# inverter_sch.net
KiCad netlist of a schematic drawn in Altium Designer
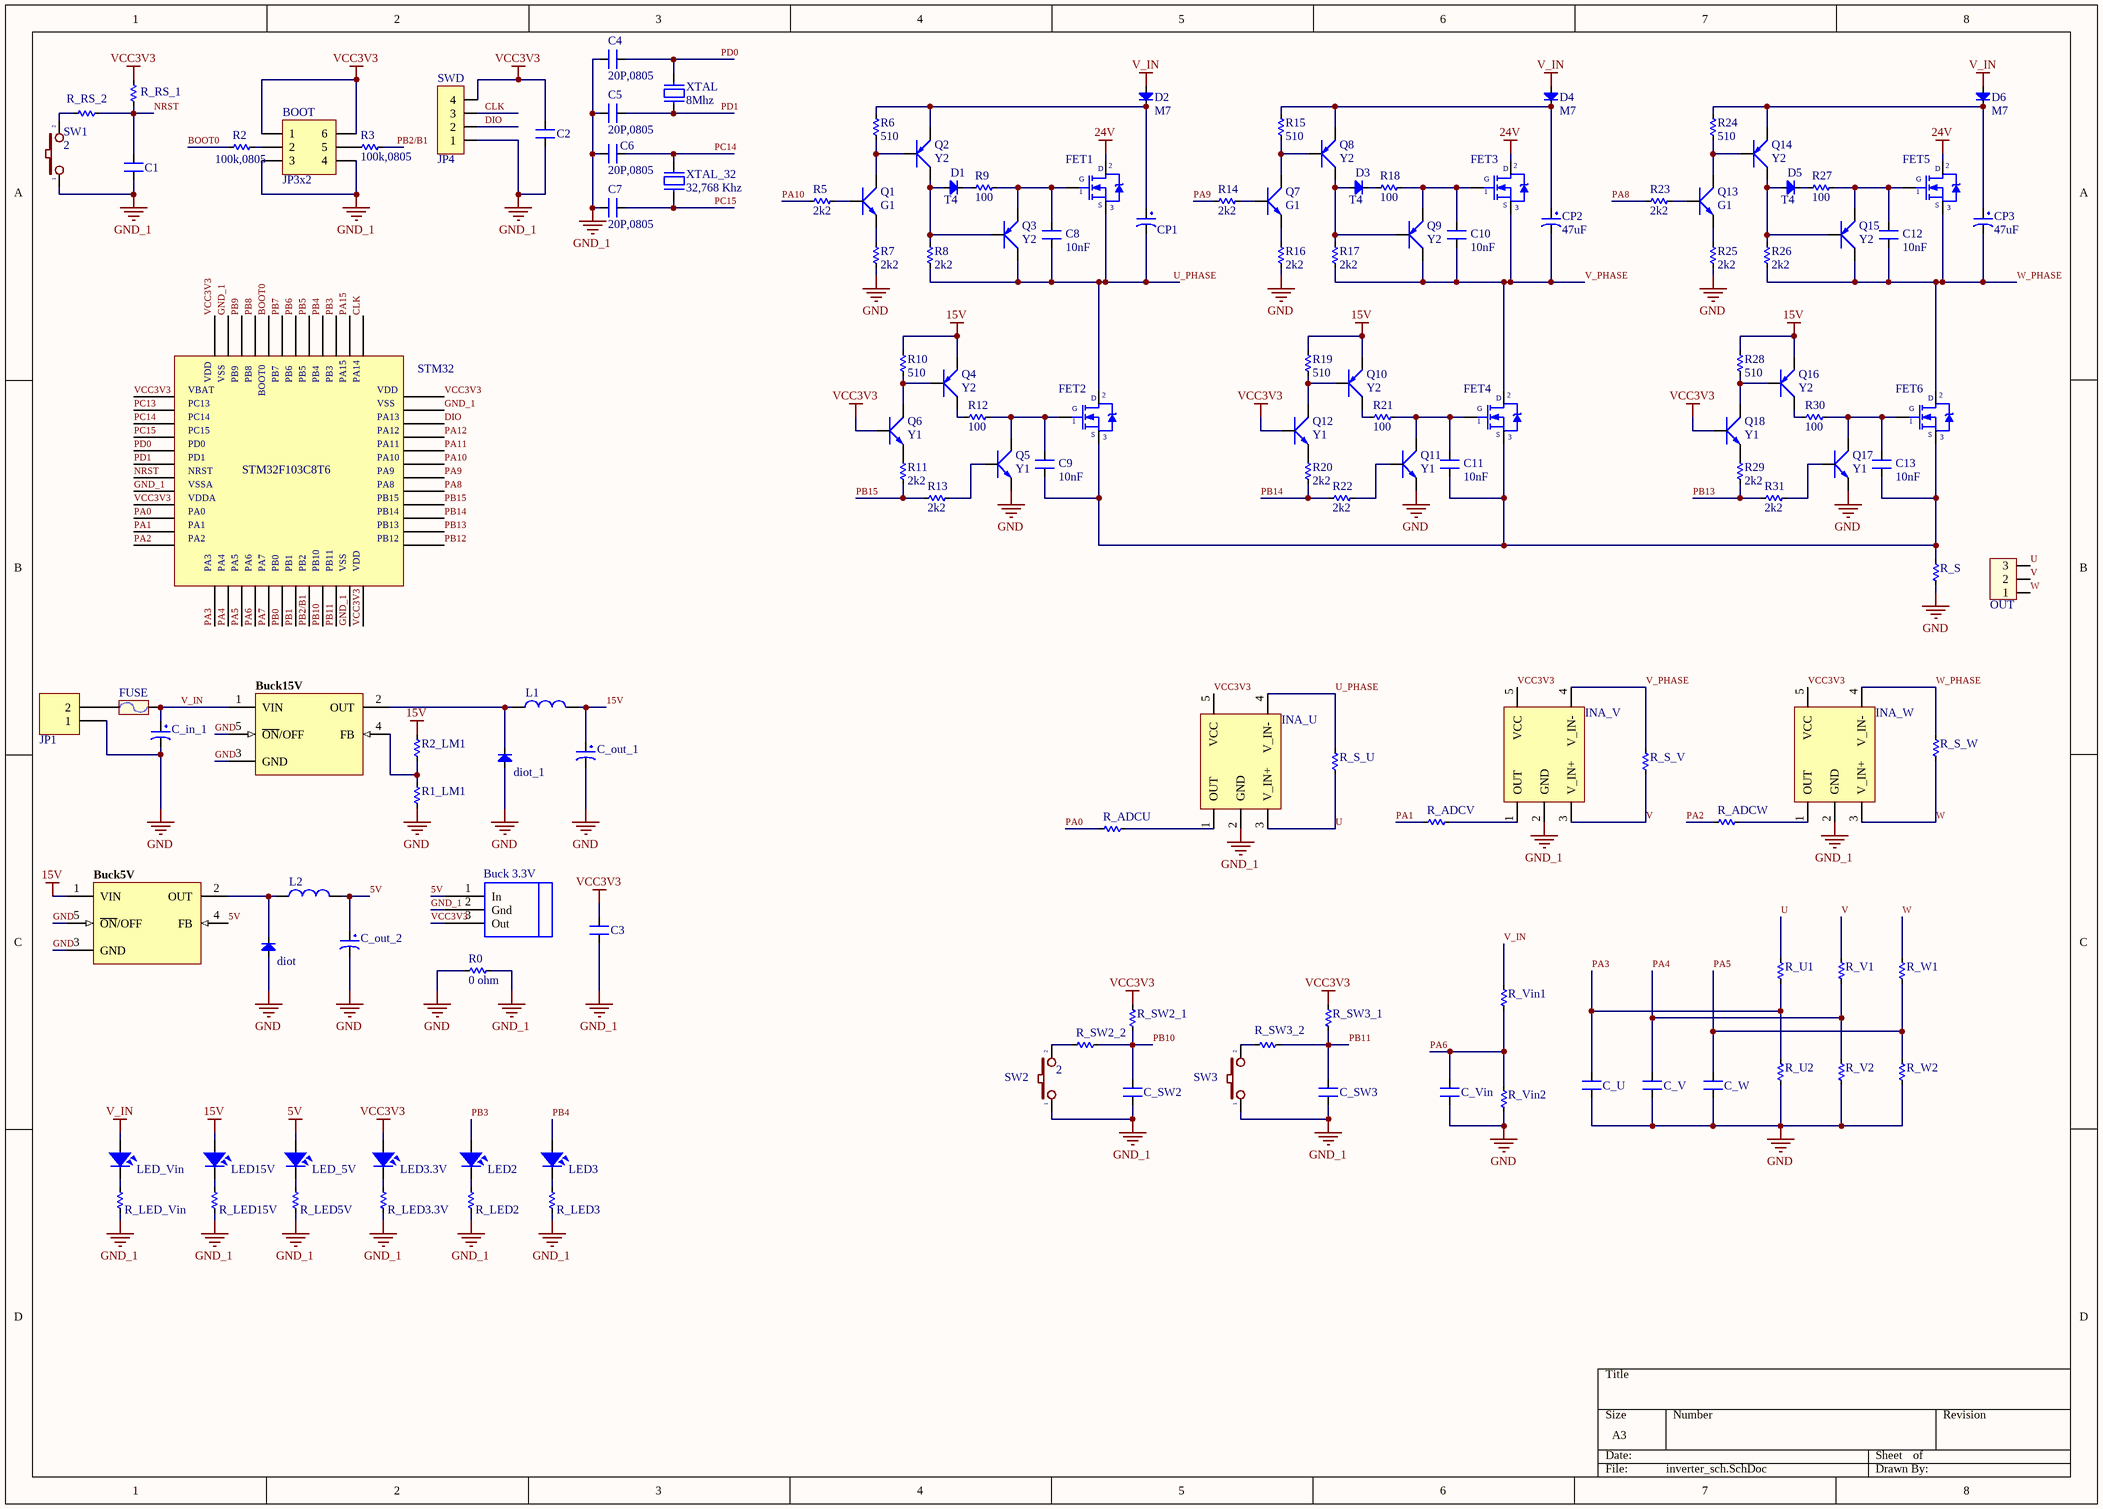
[diagram p0: inverter_sch.SchDoc]

(export (version "E")
  (design (tool "Eeschema 10.0.6"))
  (components
    (comp (ref "BOOT")
      (value "JP3x2")
      (footprint "JP3-D2T")
      (description "WR-PHD 2.54 mm Dual Socket Header")
      (fields
        (field (name "MANUFACTURER") "Würth Elektronik eiSos GmbH")
        (field (name "PARTNO") "61300621821")
        (field (name "CREATED BY") "Karrer Zheng")
      )
      (libsource (lib "LIBRARY") (part "JP3x2"))
    )
    (comp (ref "Buck 3.3V")
      (value "LM3940-3.3")
      (footprint "SOT223")
      (description "3.3 VOLT LINEAR REGULATOR SOT223")
      (fields
        (field (name "MANUFACTURER") "National Semiconductor")
        (field (name "MANUFACTURER PART NUMBER") "LM3940IMP-3.3/NOPB")
      )
      (libsource (lib "LIBRARY") (part "LM3940-3.3-SOT223"))
    )
    (comp (ref "Buck5V") (value "LM2576") (footprint "TO263") (libsource (lib "LIBRARY") (part "LM2576")))
    (comp (ref "Buck15V") (value "LM2576") (footprint "TO263") (libsource (lib "LIBRARY") (part "LM2576")))
    (comp (ref "C1") (value "104,0805") (footprint "CN-SMD-0805") (libsource (lib "LIBRARY") (part "CN")))
    (comp (ref "C2") (value "104,0805") (footprint "CN-SMD-0805") (libsource (lib "LIBRARY") (part "CN")))
    (comp (ref "C3") (value "104,0805") (footprint "CN-SMD-0805") (libsource (lib "LIBRARY") (part "CN")))
    (comp (ref "C4") (value "20P,0805") (footprint "CN-SMD-0805") (libsource (lib "LIBRARY") (part "CN")))
    (comp (ref "C5") (value "20P,0805") (footprint "CN-SMD-0805") (libsource (lib "LIBRARY") (part "CN")))
    (comp (ref "C6") (value "20P,0805") (footprint "CN-SMD-0805") (libsource (lib "LIBRARY") (part "CN")))
    (comp (ref "C7") (value "20P,0805") (footprint "CN-SMD-0805") (libsource (lib "LIBRARY") (part "CN")))
    (comp (ref "C8") (value "10nF") (footprint "CN-SMD-0805") (libsource (lib "LIBRARY") (part "CN")))
    (comp (ref "C9") (value "10nF") (footprint "CN-SMD-0805") (libsource (lib "LIBRARY") (part "CN")))
    (comp (ref "C10") (value "10nF") (footprint "CN-SMD-0805") (libsource (lib "LIBRARY") (part "CN")))
    (comp (ref "C11") (value "10nF") (footprint "CN-SMD-0805") (libsource (lib "LIBRARY") (part "CN")))
    (comp (ref "C12") (value "10nF") (footprint "CN-SMD-0805") (libsource (lib "LIBRARY") (part "CN")))
    (comp (ref "C13") (value "10nF") (footprint "CN-SMD-0805") (libsource (lib "LIBRARY") (part "CN")))
    (comp (ref "CP1")
      (value "47uF")
      (footprint "CP1/2")
      (description "Cap P  0,1uF < 22uF , 16 - 50V")
      (libsource (lib "syhaunguyen") (part "CP1"))
    )
    (comp (ref "CP2")
      (value "47uF")
      (footprint "CP1/2")
      (description "Cap P  0,1uF < 22uF , 16 - 50V")
      (libsource (lib "syhaunguyen") (part "CP1"))
    )
    (comp (ref "CP3")
      (value "47uF")
      (footprint "CP1/2")
      (description "Cap P  0,1uF < 22uF , 16 - 50V")
      (libsource (lib "syhaunguyen") (part "CP1"))
    )
    (comp (ref "C_in_1")
      (value "100uF")
      (footprint "CP1.5/3.4")
      (description "Cap 1000uF/16V - 220uF/50V")
      (libsource (lib "syhaunguyen") (part "CP4"))
    )
    (comp (ref "C_out_1")
      (value "100uF")
      (footprint "CP1.5/3.4")
      (description "Cap 1000uF/16V - 220uF/50V")
      (libsource (lib "syhaunguyen") (part "CP4"))
    )
    (comp (ref "C_out_2")
      (value "100uF")
      (footprint "CP1.5/3.4")
      (description "Cap 1000uF/16V - 220uF/50V")
      (libsource (lib "syhaunguyen") (part "CP4"))
    )
    (comp (ref "C_SW2") (value "104,0805") (footprint "CN-SMD-0805") (libsource (lib "LIBRARY") (part "CN")))
    (comp (ref "C_SW3") (value "104,0805") (footprint "CN-SMD-0805") (libsource (lib "LIBRARY") (part "CN")))
    (comp (ref "C_U") (value "XXpF") (footprint "CN-SMD-0805") (libsource (lib "LIBRARY") (part "CN")))
    (comp (ref "C_V") (value "XXpF") (footprint "CN-SMD-0805") (libsource (lib "LIBRARY") (part "CN")))
    (comp (ref "C_Vin") (value "XXpF") (footprint "CN-SMD-0805") (libsource (lib "LIBRARY") (part "CN")))
    (comp (ref "C_W") (value "XXpF") (footprint "CN-SMD-0805") (libsource (lib "LIBRARY") (part "CN")))
    (comp (ref "D1")
      (value "T4")
      (footprint "DIO-SMD-106")
      (description "Default Diode")
      (fields (field (name "PUBLISHER") "Altium Limited"))
      (libsource (lib "LIBRARY") (part "Diode SMD"))
    )
    (comp (ref "D2")
      (value "M7")
      (footprint "DIO-SMD-106")
      (description "Default Diode")
      (fields (field (name "PUBLISHER") "Altium Limited"))
      (libsource (lib "LIBRARY") (part "Diode SMD"))
    )
    (comp (ref "D3")
      (value "T4")
      (footprint "DIO-SMD-106")
      (description "Default Diode")
      (fields (field (name "PUBLISHER") "Altium Limited"))
      (libsource (lib "LIBRARY") (part "Diode SMD"))
    )
    (comp (ref "D4")
      (value "M7")
      (footprint "DIO-SMD-106")
      (description "Default Diode")
      (fields (field (name "PUBLISHER") "Altium Limited"))
      (libsource (lib "LIBRARY") (part "Diode SMD"))
    )
    (comp (ref "D5")
      (value "T4")
      (footprint "DIO-SMD-106")
      (description "Default Diode")
      (fields (field (name "PUBLISHER") "Altium Limited"))
      (libsource (lib "LIBRARY") (part "Diode SMD"))
    )
    (comp (ref "D6")
      (value "M7")
      (footprint "DIO-SMD-106")
      (description "Default Diode")
      (fields (field (name "PUBLISHER") "Altium Limited"))
      (libsource (lib "LIBRARY") (part "Diode SMD"))
    )
    (comp (ref "diot")
      (value "Diode SMD")
      (footprint "DIO-SMD-106")
      (description "Default Diode")
      (fields (field (name "PUBLISHER") "Altium Limited"))
      (libsource (lib "LIBRARY") (part "Diode SMD"))
    )
    (comp (ref "diot_1")
      (value "Diode SMD")
      (footprint "DIO-SMD-106")
      (description "Default Diode")
      (fields (field (name "PUBLISHER") "Altium Limited"))
      (libsource (lib "LIBRARY") (part "Diode SMD"))
    )
    (comp (ref "FET1")
      (value "STP80NF70")
      (footprint "QTO-220")
      (description "MOSFET N - CHANNEL 500V - 0.75 - 8A - TO-220")
      (libsource (lib "syhaunguyen") (part "IRF840"))
    )
    (comp (ref "FET2")
      (value "STP80NF70")
      (footprint "QTO-220")
      (description "MOSFET N - CHANNEL 500V - 0.75 - 8A - TO-220")
      (libsource (lib "syhaunguyen") (part "IRF840"))
    )
    (comp (ref "FET3")
      (value "STP80NF70")
      (footprint "QTO-220")
      (description "MOSFET N - CHANNEL 500V - 0.75 - 8A - TO-220")
      (libsource (lib "syhaunguyen") (part "IRF840"))
    )
    (comp (ref "FET4")
      (value "STP80NF70")
      (footprint "QTO-220")
      (description "MOSFET N - CHANNEL 500V - 0.75 - 8A - TO-220")
      (libsource (lib "syhaunguyen") (part "IRF840"))
    )
    (comp (ref "FET5")
      (value "STP80NF70")
      (footprint "QTO-220")
      (description "MOSFET N - CHANNEL 500V - 0.75 - 8A - TO-220")
      (libsource (lib "syhaunguyen") (part "IRF840"))
    )
    (comp (ref "FET6")
      (value "STP80NF70")
      (footprint "QTO-220")
      (description "MOSFET N - CHANNEL 500V - 0.75 - 8A - TO-220")
      (libsource (lib "syhaunguyen") (part "IRF840"))
    )
    (comp (ref "FUSE")
      (value "F1A")
      (footprint "Fuse1")
      (description "Fuse")
      (fields (field (name "DESIGNED BY") "VanDungEvn"))
      (libsource (lib "LIBRARY") (part "Fuse"))
    )
    (comp (ref "INA_U")
      (value "INA193_4_5")
      (footprint "SOT95_SOT23")
      (libsource (lib "Schlib1") (part "INA193_4_5"))
    )
    (comp (ref "INA_V")
      (value "INA193_4_5")
      (footprint "SOT95_SOT23")
      (libsource (lib "Schlib1") (part "INA193_4_5"))
    )
    (comp (ref "INA_W")
      (value "INA193_4_5")
      (footprint "SOT95_SOT23")
      (libsource (lib "Schlib1") (part "INA193_4_5"))
    )
    (comp (ref "JP1")
      (value "Header 2_1")
      (footprint "HED2")
      (description "Header, 2-Pin")
      (fields (field (name "MANUFACTURER") "Generic Components"))
      (libsource (lib "syhaunguyen") (part "Header 2_1"))
    )
    (comp (ref "L1")
      (value "100mH")
      (footprint "L/0.4")
      (description "Inductor")
      (libsource (lib "syhaunguyen") (part "L1"))
    )
    (comp (ref "L2")
      (value "100mH")
      (footprint "L/0.4")
      (description "Inductor")
      (libsource (lib "syhaunguyen") (part "L1"))
    )
    (comp (ref "LED2")
      (value "power 0805")
      (footprint "LED-0805-Blue")
      (libsource (lib "LIBRARY") (part "LED SMD"))
    )
    (comp (ref "LED3")
      (value "power 0805")
      (footprint "LED-0805-Blue")
      (libsource (lib "LIBRARY") (part "LED SMD"))
    )
    (comp (ref "LED3.3V")
      (value "power 0805")
      (footprint "LED-0805-Blue")
      (libsource (lib "LIBRARY") (part "LED SMD"))
    )
    (comp (ref "LED15V")
      (value "power 0805")
      (footprint "LED-0805-Blue")
      (libsource (lib "LIBRARY") (part "LED SMD"))
    )
    (comp (ref "LED_5V")
      (value "power 0805")
      (footprint "LED-0805-Blue")
      (libsource (lib "LIBRARY") (part "LED SMD"))
    )
    (comp (ref "LED_Vin")
      (value "power 0805")
      (footprint "LED-0805-Blue")
      (libsource (lib "LIBRARY") (part "LED SMD"))
    )
    (comp (ref "OUT")
      (value "Header 3")
      (footprint "HED3B")
      (description "Header 3 (Green)")
      (libsource (lib "syhaunguyen") (part "Hed3"))
    )
    (comp (ref "Q1")
      (value "G1")
      (footprint "SOT23B")
      (description "NPN 600mW, ECB")
      (libsource (lib "syhaunguyen") (part "C1815"))
    )
    (comp (ref "Q2")
      (value "Y2")
      (footprint "SOT23B")
      (description "PNP 600mW, ECB")
      (libsource (lib "syhaunguyen") (part "A1015"))
    )
    (comp (ref "Q3")
      (value "Y2")
      (footprint "SOT23B")
      (description "PNP 600mW, ECB")
      (libsource (lib "syhaunguyen") (part "A1015"))
    )
    (comp (ref "Q4")
      (value "Y2")
      (footprint "SOT23B")
      (description "PNP 600mW, ECB")
      (libsource (lib "syhaunguyen") (part "A1015"))
    )
    (comp (ref "Q5")
      (value "Y1")
      (footprint "SOT23B")
      (description "NPN 600mW, ECB")
      (libsource (lib "syhaunguyen") (part "C1815"))
    )
    (comp (ref "Q6")
      (value "Y1")
      (footprint "SOT23B")
      (description "NPN 600mW, ECB")
      (libsource (lib "syhaunguyen") (part "C1815"))
    )
    (comp (ref "Q7")
      (value "G1")
      (footprint "SOT23B")
      (description "NPN 600mW, ECB")
      (libsource (lib "syhaunguyen") (part "C1815"))
    )
    (comp (ref "Q8")
      (value "Y2")
      (footprint "SOT23B")
      (description "PNP 600mW, ECB")
      (libsource (lib "syhaunguyen") (part "A1015"))
    )
    (comp (ref "Q9")
      (value "Y2")
      (footprint "SOT23B")
      (description "PNP 600mW, ECB")
      (libsource (lib "syhaunguyen") (part "A1015"))
    )
    (comp (ref "Q10")
      (value "Y2")
      (footprint "SOT23B")
      (description "PNP 600mW, ECB")
      (libsource (lib "syhaunguyen") (part "A1015"))
    )
    (comp (ref "Q11")
      (value "Y1")
      (footprint "SOT23B")
      (description "NPN 600mW, ECB")
      (libsource (lib "syhaunguyen") (part "C1815"))
    )
    (comp (ref "Q12")
      (value "Y1")
      (footprint "SOT23B")
      (description "NPN 600mW, ECB")
      (libsource (lib "syhaunguyen") (part "C1815"))
    )
    (comp (ref "Q13")
      (value "G1")
      (footprint "SOT23B")
      (description "NPN 600mW, ECB")
      (libsource (lib "syhaunguyen") (part "C1815"))
    )
    (comp (ref "Q14")
      (value "Y2")
      (footprint "SOT23B")
      (description "PNP 600mW, ECB")
      (libsource (lib "syhaunguyen") (part "A1015"))
    )
    (comp (ref "Q15")
      (value "Y2")
      (footprint "SOT23B")
      (description "PNP 600mW, ECB")
      (libsource (lib "syhaunguyen") (part "A1015"))
    )
    (comp (ref "Q16")
      (value "Y2")
      (footprint "SOT23B")
      (description "PNP 600mW, ECB")
      (libsource (lib "syhaunguyen") (part "A1015"))
    )
    (comp (ref "Q17")
      (value "Y1")
      (footprint "SOT23B")
      (description "NPN 600mW, ECB")
      (libsource (lib "syhaunguyen") (part "C1815"))
    )
    (comp (ref "Q18")
      (value "Y1")
      (footprint "SOT23B")
      (description "NPN 600mW, ECB")
      (libsource (lib "syhaunguyen") (part "C1815"))
    )
    (comp (ref "R0")
      (value "0 ohm")
      (footprint "RES-SMD-1206")
      (description "Resistor")
      (fields
        (field (name "MANUFACTURER") "Generic Components")
        (field (name "PUBLISHER") "Altium Hobart Technology Centre")
      )
      (libsource (lib "LIBRARY") (part "Res-SMD"))
    )
    (comp (ref "R1_LM1")
      (value "Res")
      (footprint "RES-SMD-0805")
      (description "Resistor")
      (fields
        (field (name "MANUFACTURER") "Generic Components")
        (field (name "PUBLISHER") "Altium Hobart Technology Centre")
      )
      (libsource (lib "LIBRARY") (part "Res-SMD"))
    )
    (comp (ref "R2")
      (value "100k,0805")
      (footprint "RES-SMD-0805")
      (description "Resistor")
      (fields
        (field (name "MANUFACTURER") "Generic Components")
        (field (name "PUBLISHER") "Altium Hobart Technology Centre")
      )
      (libsource (lib "LIBRARY") (part "Res-SMD"))
    )
    (comp (ref "R2_LM1")
      (value "Res")
      (footprint "RES-SMD-0805")
      (description "Resistor")
      (fields
        (field (name "MANUFACTURER") "Generic Components")
        (field (name "PUBLISHER") "Altium Hobart Technology Centre")
      )
      (libsource (lib "LIBRARY") (part "Res-SMD"))
    )
    (comp (ref "R3")
      (value "100k,0805")
      (footprint "RES-SMD-0805")
      (description "Resistor")
      (fields
        (field (name "MANUFACTURER") "Generic Components")
        (field (name "PUBLISHER") "Altium Hobart Technology Centre")
      )
      (libsource (lib "LIBRARY") (part "Res-SMD"))
    )
    (comp (ref "R5")
      (value "2k2")
      (footprint "RES-SMD-0805")
      (description "Resistor")
      (fields
        (field (name "MANUFACTURER") "Generic Components")
        (field (name "PUBLISHER") "Altium Hobart Technology Centre")
      )
      (libsource (lib "LIBRARY") (part "Res-SMD"))
    )
    (comp (ref "R6")
      (value "510")
      (footprint "RES-SMD-0805")
      (description "Resistor")
      (fields
        (field (name "MANUFACTURER") "Generic Components")
        (field (name "PUBLISHER") "Altium Hobart Technology Centre")
      )
      (libsource (lib "LIBRARY") (part "Res-SMD"))
    )
    (comp (ref "R7")
      (value "2k2")
      (footprint "RES-SMD-0805")
      (description "Resistor")
      (fields
        (field (name "MANUFACTURER") "Generic Components")
        (field (name "PUBLISHER") "Altium Hobart Technology Centre")
      )
      (libsource (lib "LIBRARY") (part "Res-SMD"))
    )
    (comp (ref "R8")
      (value "2k2")
      (footprint "RES-SMD-0805")
      (description "Resistor")
      (fields
        (field (name "MANUFACTURER") "Generic Components")
        (field (name "PUBLISHER") "Altium Hobart Technology Centre")
      )
      (libsource (lib "LIBRARY") (part "Res-SMD"))
    )
    (comp (ref "R9")
      (value "100")
      (footprint "RES-SMD-0805")
      (description "Resistor")
      (fields
        (field (name "MANUFACTURER") "Generic Components")
        (field (name "PUBLISHER") "Altium Hobart Technology Centre")
      )
      (libsource (lib "LIBRARY") (part "Res-SMD"))
    )
    (comp (ref "R10")
      (value "510")
      (footprint "RES-SMD-0805")
      (description "Resistor")
      (fields
        (field (name "MANUFACTURER") "Generic Components")
        (field (name "PUBLISHER") "Altium Hobart Technology Centre")
      )
      (libsource (lib "LIBRARY") (part "Res-SMD"))
    )
    (comp (ref "R11")
      (value "2k2")
      (footprint "RES-SMD-0805")
      (description "Resistor")
      (fields
        (field (name "MANUFACTURER") "Generic Components")
        (field (name "PUBLISHER") "Altium Hobart Technology Centre")
      )
      (libsource (lib "LIBRARY") (part "Res-SMD"))
    )
    (comp (ref "R12")
      (value "100")
      (footprint "RES-SMD-0805")
      (description "Resistor")
      (fields
        (field (name "MANUFACTURER") "Generic Components")
        (field (name "PUBLISHER") "Altium Hobart Technology Centre")
      )
      (libsource (lib "LIBRARY") (part "Res-SMD"))
    )
    (comp (ref "R13")
      (value "2k2")
      (footprint "RES-SMD-0805")
      (description "Resistor")
      (fields
        (field (name "MANUFACTURER") "Generic Components")
        (field (name "PUBLISHER") "Altium Hobart Technology Centre")
      )
      (libsource (lib "LIBRARY") (part "Res-SMD"))
    )
    (comp (ref "R14")
      (value "2k2")
      (footprint "RES-SMD-0805")
      (description "Resistor")
      (fields
        (field (name "MANUFACTURER") "Generic Components")
        (field (name "PUBLISHER") "Altium Hobart Technology Centre")
      )
      (libsource (lib "LIBRARY") (part "Res-SMD"))
    )
    (comp (ref "R15")
      (value "510")
      (footprint "RES-SMD-0805")
      (description "Resistor")
      (fields
        (field (name "MANUFACTURER") "Generic Components")
        (field (name "PUBLISHER") "Altium Hobart Technology Centre")
      )
      (libsource (lib "LIBRARY") (part "Res-SMD"))
    )
    (comp (ref "R16")
      (value "2k2")
      (footprint "RES-SMD-0805")
      (description "Resistor")
      (fields
        (field (name "MANUFACTURER") "Generic Components")
        (field (name "PUBLISHER") "Altium Hobart Technology Centre")
      )
      (libsource (lib "LIBRARY") (part "Res-SMD"))
    )
    (comp (ref "R17")
      (value "2k2")
      (footprint "RES-SMD-0805")
      (description "Resistor")
      (fields
        (field (name "MANUFACTURER") "Generic Components")
        (field (name "PUBLISHER") "Altium Hobart Technology Centre")
      )
      (libsource (lib "LIBRARY") (part "Res-SMD"))
    )
    (comp (ref "R18")
      (value "100")
      (footprint "RES-SMD-0805")
      (description "Resistor")
      (fields
        (field (name "MANUFACTURER") "Generic Components")
        (field (name "PUBLISHER") "Altium Hobart Technology Centre")
      )
      (libsource (lib "LIBRARY") (part "Res-SMD"))
    )
    (comp (ref "R19")
      (value "510")
      (footprint "RES-SMD-0805")
      (description "Resistor")
      (fields
        (field (name "MANUFACTURER") "Generic Components")
        (field (name "PUBLISHER") "Altium Hobart Technology Centre")
      )
      (libsource (lib "LIBRARY") (part "Res-SMD"))
    )
    (comp (ref "R20")
      (value "2k2")
      (footprint "RES-SMD-0805")
      (description "Resistor")
      (fields
        (field (name "MANUFACTURER") "Generic Components")
        (field (name "PUBLISHER") "Altium Hobart Technology Centre")
      )
      (libsource (lib "LIBRARY") (part "Res-SMD"))
    )
    (comp (ref "R21")
      (value "100")
      (footprint "RES-SMD-0805")
      (description "Resistor")
      (fields
        (field (name "MANUFACTURER") "Generic Components")
        (field (name "PUBLISHER") "Altium Hobart Technology Centre")
      )
      (libsource (lib "LIBRARY") (part "Res-SMD"))
    )
    (comp (ref "R22")
      (value "2k2")
      (footprint "RES-SMD-0805")
      (description "Resistor")
      (fields
        (field (name "MANUFACTURER") "Generic Components")
        (field (name "PUBLISHER") "Altium Hobart Technology Centre")
      )
      (libsource (lib "LIBRARY") (part "Res-SMD"))
    )
    (comp (ref "R23")
      (value "2k2")
      (footprint "RES-SMD-0805")
      (description "Resistor")
      (fields
        (field (name "MANUFACTURER") "Generic Components")
        (field (name "PUBLISHER") "Altium Hobart Technology Centre")
      )
      (libsource (lib "LIBRARY") (part "Res-SMD"))
    )
    (comp (ref "R24")
      (value "510")
      (footprint "RES-SMD-0805")
      (description "Resistor")
      (fields
        (field (name "MANUFACTURER") "Generic Components")
        (field (name "PUBLISHER") "Altium Hobart Technology Centre")
      )
      (libsource (lib "LIBRARY") (part "Res-SMD"))
    )
    (comp (ref "R25")
      (value "2k2")
      (footprint "RES-SMD-0805")
      (description "Resistor")
      (fields
        (field (name "MANUFACTURER") "Generic Components")
        (field (name "PUBLISHER") "Altium Hobart Technology Centre")
      )
      (libsource (lib "LIBRARY") (part "Res-SMD"))
    )
    (comp (ref "R26")
      (value "2k2")
      (footprint "RES-SMD-0805")
      (description "Resistor")
      (fields
        (field (name "MANUFACTURER") "Generic Components")
        (field (name "PUBLISHER") "Altium Hobart Technology Centre")
      )
      (libsource (lib "LIBRARY") (part "Res-SMD"))
    )
    (comp (ref "R27")
      (value "100")
      (footprint "RES-SMD-0805")
      (description "Resistor")
      (fields
        (field (name "MANUFACTURER") "Generic Components")
        (field (name "PUBLISHER") "Altium Hobart Technology Centre")
      )
      (libsource (lib "LIBRARY") (part "Res-SMD"))
    )
    (comp (ref "R28")
      (value "510")
      (footprint "RES-SMD-0805")
      (description "Resistor")
      (fields
        (field (name "MANUFACTURER") "Generic Components")
        (field (name "PUBLISHER") "Altium Hobart Technology Centre")
      )
      (libsource (lib "LIBRARY") (part "Res-SMD"))
    )
    (comp (ref "R29")
      (value "2k2")
      (footprint "RES-SMD-0805")
      (description "Resistor")
      (fields
        (field (name "MANUFACTURER") "Generic Components")
        (field (name "PUBLISHER") "Altium Hobart Technology Centre")
      )
      (libsource (lib "LIBRARY") (part "Res-SMD"))
    )
    (comp (ref "R30")
      (value "100")
      (footprint "RES-SMD-0805")
      (description "Resistor")
      (fields
        (field (name "MANUFACTURER") "Generic Components")
        (field (name "PUBLISHER") "Altium Hobart Technology Centre")
      )
      (libsource (lib "LIBRARY") (part "Res-SMD"))
    )
    (comp (ref "R31")
      (value "2k2")
      (footprint "RES-SMD-0805")
      (description "Resistor")
      (fields
        (field (name "MANUFACTURER") "Generic Components")
        (field (name "PUBLISHER") "Altium Hobart Technology Centre")
      )
      (libsource (lib "LIBRARY") (part "Res-SMD"))
    )
    (comp (ref "R_ADCU")
      (value "Res")
      (footprint "RES-SMD-0805")
      (description "Resistor")
      (fields
        (field (name "MANUFACTURER") "Generic Components")
        (field (name "PUBLISHER") "Altium Hobart Technology Centre")
      )
      (libsource (lib "LIBRARY") (part "Res-SMD"))
    )
    (comp (ref "R_ADCV")
      (value "Res")
      (footprint "RES-SMD-0805")
      (description "Resistor")
      (fields
        (field (name "MANUFACTURER") "Generic Components")
        (field (name "PUBLISHER") "Altium Hobart Technology Centre")
      )
      (libsource (lib "LIBRARY") (part "Res-SMD"))
    )
    (comp (ref "R_ADCW")
      (value "Res")
      (footprint "RES-SMD-0805")
      (description "Resistor")
      (fields
        (field (name "MANUFACTURER") "Generic Components")
        (field (name "PUBLISHER") "Altium Hobart Technology Centre")
      )
      (libsource (lib "LIBRARY") (part "Res-SMD"))
    )
    (comp (ref "R_LED2")
      (value "510,0805")
      (footprint "RES-SMD-0805")
      (description "Resistor")
      (fields
        (field (name "MANUFACTURER") "Generic Components")
        (field (name "PUBLISHER") "Altium Hobart Technology Centre")
      )
      (libsource (lib "LIBRARY") (part "Res-SMD"))
    )
    (comp (ref "R_LED3")
      (value "510,0805")
      (footprint "RES-SMD-0805")
      (description "Resistor")
      (fields
        (field (name "MANUFACTURER") "Generic Components")
        (field (name "PUBLISHER") "Altium Hobart Technology Centre")
      )
      (libsource (lib "LIBRARY") (part "Res-SMD"))
    )
    (comp (ref "R_LED3.3V")
      (value "510,0805")
      (footprint "RES-SMD-0805")
      (description "Resistor")
      (fields
        (field (name "MANUFACTURER") "Generic Components")
        (field (name "PUBLISHER") "Altium Hobart Technology Centre")
      )
      (libsource (lib "LIBRARY") (part "Res-SMD"))
    )
    (comp (ref "R_LED5V")
      (value "510,0805")
      (footprint "RES-SMD-0805")
      (description "Resistor")
      (fields
        (field (name "MANUFACTURER") "Generic Components")
        (field (name "PUBLISHER") "Altium Hobart Technology Centre")
      )
      (libsource (lib "LIBRARY") (part "Res-SMD"))
    )
    (comp (ref "R_LED15V")
      (value "510,0805")
      (footprint "RES-SMD-0805")
      (description "Resistor")
      (fields
        (field (name "MANUFACTURER") "Generic Components")
        (field (name "PUBLISHER") "Altium Hobart Technology Centre")
      )
      (libsource (lib "LIBRARY") (part "Res-SMD"))
    )
    (comp (ref "R_LED_Vin")
      (value "510,0805")
      (footprint "RES-SMD-0805")
      (description "Resistor")
      (fields
        (field (name "MANUFACTURER") "Generic Components")
        (field (name "PUBLISHER") "Altium Hobart Technology Centre")
      )
      (libsource (lib "LIBRARY") (part "Res-SMD"))
    )
    (comp (ref "R_RS_1")
      (value "10k,0805")
      (footprint "RES-SMD-0805")
      (description "Resistor")
      (fields
        (field (name "MANUFACTURER") "Generic Components")
        (field (name "PUBLISHER") "Altium Hobart Technology Centre")
      )
      (libsource (lib "LIBRARY") (part "Res-SMD"))
    )
    (comp (ref "R_RS_2")
      (value "10k,0805")
      (footprint "RES-SMD-0805")
      (description "Resistor")
      (fields
        (field (name "MANUFACTURER") "Generic Components")
        (field (name "PUBLISHER") "Altium Hobart Technology Centre")
      )
      (libsource (lib "LIBRARY") (part "Res-SMD"))
    )
    (comp (ref "R_S")
      (value "Res")
      (footprint "RES-SMD-2512")
      (description "Resistor")
      (fields
        (field (name "MANUFACTURER") "Generic Components")
        (field (name "PUBLISHER") "Altium Hobart Technology Centre")
      )
      (libsource (lib "LIBRARY") (part "Res-SMD"))
    )
    (comp (ref "R_SW2_1")
      (value "10k,0805")
      (footprint "RES-SMD-0805")
      (description "Resistor")
      (fields
        (field (name "MANUFACTURER") "Generic Components")
        (field (name "PUBLISHER") "Altium Hobart Technology Centre")
      )
      (libsource (lib "LIBRARY") (part "Res-SMD"))
    )
    (comp (ref "R_SW2_2")
      (value "10k,0805")
      (footprint "RES-SMD-0805")
      (description "Resistor")
      (fields
        (field (name "MANUFACTURER") "Generic Components")
        (field (name "PUBLISHER") "Altium Hobart Technology Centre")
      )
      (libsource (lib "LIBRARY") (part "Res-SMD"))
    )
    (comp (ref "R_SW3_1")
      (value "10k,0805")
      (footprint "RES-SMD-0805")
      (description "Resistor")
      (fields
        (field (name "MANUFACTURER") "Generic Components")
        (field (name "PUBLISHER") "Altium Hobart Technology Centre")
      )
      (libsource (lib "LIBRARY") (part "Res-SMD"))
    )
    (comp (ref "R_SW3_2")
      (value "10k,0805")
      (footprint "RES-SMD-0805")
      (description "Resistor")
      (fields
        (field (name "MANUFACTURER") "Generic Components")
        (field (name "PUBLISHER") "Altium Hobart Technology Centre")
      )
      (libsource (lib "LIBRARY") (part "Res-SMD"))
    )
    (comp (ref "R_S_U")
      (value "Res")
      (footprint "RES-SMD-2512")
      (description "Resistor")
      (fields
        (field (name "MANUFACTURER") "Generic Components")
        (field (name "PUBLISHER") "Altium Hobart Technology Centre")
      )
      (libsource (lib "LIBRARY") (part "Res-SMD"))
    )
    (comp (ref "R_S_V")
      (value "Res")
      (footprint "RES-SMD-2512")
      (description "Resistor")
      (fields
        (field (name "MANUFACTURER") "Generic Components")
        (field (name "PUBLISHER") "Altium Hobart Technology Centre")
      )
      (libsource (lib "LIBRARY") (part "Res-SMD"))
    )
    (comp (ref "R_S_W")
      (value "Res")
      (footprint "RES-SMD-2512")
      (description "Resistor")
      (fields
        (field (name "MANUFACTURER") "Generic Components")
        (field (name "PUBLISHER") "Altium Hobart Technology Centre")
      )
      (libsource (lib "LIBRARY") (part "Res-SMD"))
    )
    (comp (ref "R_U1")
      (value "Res")
      (footprint "RES-SMD-0805")
      (description "Resistor")
      (fields
        (field (name "MANUFACTURER") "Generic Components")
        (field (name "PUBLISHER") "Altium Hobart Technology Centre")
      )
      (libsource (lib "LIBRARY") (part "Res-SMD"))
    )
    (comp (ref "R_U2")
      (value "Res")
      (footprint "RES-SMD-0805")
      (description "Resistor")
      (fields
        (field (name "MANUFACTURER") "Generic Components")
        (field (name "PUBLISHER") "Altium Hobart Technology Centre")
      )
      (libsource (lib "LIBRARY") (part "Res-SMD"))
    )
    (comp (ref "R_V1")
      (value "Res")
      (footprint "RES-SMD-0805")
      (description "Resistor")
      (fields
        (field (name "MANUFACTURER") "Generic Components")
        (field (name "PUBLISHER") "Altium Hobart Technology Centre")
      )
      (libsource (lib "LIBRARY") (part "Res-SMD"))
    )
    (comp (ref "R_V2")
      (value "Res")
      (footprint "RES-SMD-0805")
      (description "Resistor")
      (fields
        (field (name "MANUFACTURER") "Generic Components")
        (field (name "PUBLISHER") "Altium Hobart Technology Centre")
      )
      (libsource (lib "LIBRARY") (part "Res-SMD"))
    )
    (comp (ref "R_Vin1")
      (value "Res")
      (footprint "RES-SMD-0805")
      (description "Resistor")
      (fields
        (field (name "MANUFACTURER") "Generic Components")
        (field (name "PUBLISHER") "Altium Hobart Technology Centre")
      )
      (libsource (lib "LIBRARY") (part "Res-SMD"))
    )
    (comp (ref "R_Vin2")
      (value "Res")
      (footprint "RES-SMD-0805")
      (description "Resistor")
      (fields
        (field (name "MANUFACTURER") "Generic Components")
        (field (name "PUBLISHER") "Altium Hobart Technology Centre")
      )
      (libsource (lib "LIBRARY") (part "Res-SMD"))
    )
    (comp (ref "R_W1")
      (value "Res")
      (footprint "RES-SMD-0805")
      (description "Resistor")
      (fields
        (field (name "MANUFACTURER") "Generic Components")
        (field (name "PUBLISHER") "Altium Hobart Technology Centre")
      )
      (libsource (lib "LIBRARY") (part "Res-SMD"))
    )
    (comp (ref "R_W2")
      (value "Res")
      (footprint "RES-SMD-0805")
      (description "Resistor")
      (fields
        (field (name "MANUFACTURER") "Generic Components")
        (field (name "PUBLISHER") "Altium Hobart Technology Centre")
      )
      (libsource (lib "LIBRARY") (part "Res-SMD"))
    )
    (comp (ref "STM32")
      (value "STM32F103C8T6")
      (footprint "LQFP 48")
      (fields (field (name "MANUFACTURER") "STMicroelectronics"))
      (libsource (lib "Schlib1") (part "STM32F103C8T6"))
    )
    (comp (ref "SW1")
      (value "2")
      (footprint "SW1-SMD")
      (description "Switch button 2 pin")
      (libsource (lib "LIBRARY") (part "SW2"))
    )
    (comp (ref "SW2")
      (value "2")
      (footprint "SW1-SMD")
      (description "Switch button 2 pin")
      (libsource (lib "LIBRARY") (part "SW2"))
    )
    (comp (ref "SW3")
      (value "2")
      (footprint "SW1-SMD")
      (description "Switch button 2 pin")
      (libsource (lib "LIBRARY") (part "SW2"))
    )
    (comp (ref "SWD")
      (value "JP4")
      (footprint "JP4-C1T")
      (description "WR-PHD 2.54 mm Angled Socket Header")
      (fields
        (field (name "MANUFACTURER") "Würth Elektronik eiSos GmbH")
        (field (name "PARTNO") "613004143121")
        (field (name "CREATED BY") "Karrer Zheng")
      )
      (libsource (lib "LIBRARY") (part "JP4"))
    )
    (comp (ref "XTAL")
      (value "8Mhz")
      (footprint "XT2")
      (description "Crystal, 32.768 KHz, -40 to 85 degC, 3.2 x 1.5 x 0.9 mm SMD")
      (libsource (lib "LIBRARY") (part "XT2"))
    )
    (comp (ref "XTAL_32")
      (value "32,768 Khz")
      (footprint "XT32k")
      (description "Crystal 32,768kHz for timer real")
      (libsource (lib "syhaunguyen") (part "XT32k"))
    )
  )
  (nets
    (net (code "1") (name "/BOOT0") (class "Default")
      (node (ref "R2") (pin "1") (pinfunction "1_1") (pintype "passive"))
      (node (ref "STM32") (pin "44") (pinfunction "44_44") (pintype "passive"))
    )
    (net (code "2") (name "/CLK") (class "Default")
      (node (ref "STM32") (pin "37") (pinfunction "37_37") (pintype "passive"))
      (node (ref "SWD") (pin "3") (pinfunction "3_3") (pintype "passive"))
    )
    (net (code "3") (name "/DIO") (class "Default")
      (node (ref "STM32") (pin "34") (pinfunction "34_34") (pintype "passive"))
      (node (ref "SWD") (pin "2") (pinfunction "2_2") (pintype "passive"))
    )
    (net (code "4") (name "/NRST") (class "Default")
      (node (ref "C1") (pin "2") (pinfunction "2_2") (pintype "passive"))
      (node (ref "R_RS_1") (pin "2") (pinfunction "2_2") (pintype "passive"))
      (node (ref "R_RS_2") (pin "1") (pinfunction "1_1") (pintype "passive"))
      (node (ref "STM32") (pin "7") (pinfunction "7_7") (pintype "passive"))
    )
    (net (code "5") (name "/PA0") (class "Default")
      (node (ref "R_ADCU") (pin "2") (pinfunction "2_2") (pintype "passive"))
      (node (ref "STM32") (pin "10") (pinfunction "10_10") (pintype "passive"))
    )
    (net (code "6") (name "/PA1") (class "Default")
      (node (ref "R_ADCV") (pin "2") (pinfunction "2_2") (pintype "passive"))
      (node (ref "STM32") (pin "11") (pinfunction "11_11") (pintype "passive"))
    )
    (net (code "7") (name "/PA2") (class "Default")
      (node (ref "R_ADCW") (pin "2") (pinfunction "2_2") (pintype "passive"))
      (node (ref "STM32") (pin "12") (pinfunction "12_12") (pintype "passive"))
    )
    (net (code "8") (name "/PA3") (class "Default")
      (node (ref "C_U") (pin "2") (pinfunction "2_2") (pintype "passive"))
      (node (ref "R_U1") (pin "2") (pinfunction "2_2") (pintype "passive"))
      (node (ref "R_U2") (pin "1") (pinfunction "1_1") (pintype "passive"))
      (node (ref "STM32") (pin "13") (pinfunction "13_13") (pintype "passive"))
    )
    (net (code "9") (name "/PA4") (class "Default")
      (node (ref "C_V") (pin "2") (pinfunction "2_2") (pintype "passive"))
      (node (ref "R_V1") (pin "2") (pinfunction "2_2") (pintype "passive"))
      (node (ref "R_V2") (pin "1") (pinfunction "1_1") (pintype "passive"))
      (node (ref "STM32") (pin "14") (pinfunction "14_14") (pintype "passive"))
    )
    (net (code "10") (name "/PA5") (class "Default")
      (node (ref "C_W") (pin "2") (pinfunction "2_2") (pintype "passive"))
      (node (ref "R_W1") (pin "2") (pinfunction "2_2") (pintype "passive"))
      (node (ref "R_W2") (pin "1") (pinfunction "1_1") (pintype "passive"))
      (node (ref "STM32") (pin "15") (pinfunction "15_15") (pintype "passive"))
    )
    (net (code "11") (name "/PA6") (class "Default")
      (node (ref "C_Vin") (pin "2") (pinfunction "2_2") (pintype "passive"))
      (node (ref "R_Vin1") (pin "2") (pinfunction "2_2") (pintype "passive"))
      (node (ref "R_Vin2") (pin "1") (pinfunction "1_1") (pintype "passive"))
      (node (ref "STM32") (pin "16") (pinfunction "16_16") (pintype "passive"))
    )
    (net (code "12") (name "/PA7") (class "Default")
      (node (ref "STM32") (pin "17") (pinfunction "17_17") (pintype "passive"))
    )
    (net (code "13") (name "/PA8") (class "Default")
      (node (ref "R23") (pin "2") (pinfunction "2_2") (pintype "passive"))
      (node (ref "STM32") (pin "29") (pinfunction "29_29") (pintype "passive"))
    )
    (net (code "14") (name "/PA9") (class "Default")
      (node (ref "R14") (pin "2") (pinfunction "2_2") (pintype "passive"))
      (node (ref "STM32") (pin "30") (pinfunction "30_30") (pintype "passive"))
    )
    (net (code "15") (name "/PA10") (class "Default")
      (node (ref "R5") (pin "2") (pinfunction "2_2") (pintype "passive"))
      (node (ref "STM32") (pin "31") (pinfunction "31_31") (pintype "passive"))
    )
    (net (code "16") (name "/PA11") (class "Default")
      (node (ref "STM32") (pin "32") (pinfunction "32_32") (pintype "passive"))
    )
    (net (code "17") (name "/PA12") (class "Default")
      (node (ref "STM32") (pin "33") (pinfunction "33_33") (pintype "passive"))
    )
    (net (code "18") (name "/PA15") (class "Default")
      (node (ref "STM32") (pin "38") (pinfunction "38_38") (pintype "passive"))
    )
    (net (code "19") (name "/PB0") (class "Default")
      (node (ref "STM32") (pin "18") (pinfunction "18_18") (pintype "passive"))
    )
    (net (code "20") (name "/PB1") (class "Default")
      (node (ref "STM32") (pin "19") (pinfunction "19_19") (pintype "passive"))
    )
    (net (code "21") (name "/PB2{slash}B1") (class "Default")
      (node (ref "R3") (pin "1") (pinfunction "1_1") (pintype "passive"))
      (node (ref "STM32") (pin "20") (pinfunction "20_20") (pintype "passive"))
    )
    (net (code "22") (name "/PB3") (class "Default")
      (node (ref "LED2") (pin "1") (pinfunction "1_1") (pintype "passive"))
      (node (ref "STM32") (pin "39") (pinfunction "39_39") (pintype "passive"))
    )
    (net (code "23") (name "/PB4") (class "Default")
      (node (ref "LED3") (pin "1") (pinfunction "1_1") (pintype "passive"))
      (node (ref "STM32") (pin "40") (pinfunction "40_40") (pintype "passive"))
    )
    (net (code "24") (name "/PB5") (class "Default")
      (node (ref "STM32") (pin "41") (pinfunction "41_41") (pintype "passive"))
    )
    (net (code "25") (name "/PB6") (class "Default")
      (node (ref "STM32") (pin "42") (pinfunction "42_42") (pintype "passive"))
    )
    (net (code "26") (name "/PB7") (class "Default")
      (node (ref "STM32") (pin "43") (pinfunction "43_43") (pintype "passive"))
    )
    (net (code "27") (name "/PB8") (class "Default")
      (node (ref "STM32") (pin "45") (pinfunction "45_45") (pintype "passive"))
    )
    (net (code "28") (name "/PB9") (class "Default")
      (node (ref "STM32") (pin "46") (pinfunction "46_46") (pintype "passive"))
    )
    (net (code "29") (name "/PB10") (class "Default")
      (node (ref "C_SW2") (pin "2") (pinfunction "2_2") (pintype "passive"))
      (node (ref "R_SW2_1") (pin "2") (pinfunction "2_2") (pintype "passive"))
      (node (ref "R_SW2_2") (pin "2") (pinfunction "2_2") (pintype "passive"))
      (node (ref "STM32") (pin "21") (pinfunction "21_21") (pintype "passive"))
    )
    (net (code "30") (name "/PB11") (class "Default")
      (node (ref "C_SW3") (pin "2") (pinfunction "2_2") (pintype "passive"))
      (node (ref "R_SW3_1") (pin "2") (pinfunction "2_2") (pintype "passive"))
      (node (ref "R_SW3_2") (pin "2") (pinfunction "2_2") (pintype "passive"))
      (node (ref "STM32") (pin "22") (pinfunction "22_22") (pintype "passive"))
    )
    (net (code "31") (name "/PB12") (class "Default")
      (node (ref "STM32") (pin "25") (pinfunction "25_25") (pintype "passive"))
    )
    (net (code "32") (name "/PB13") (class "Default")
      (node (ref "R29") (pin "2") (pinfunction "2_2") (pintype "passive"))
      (node (ref "R31") (pin "1") (pinfunction "1_1") (pintype "passive"))
      (node (ref "STM32") (pin "26") (pinfunction "26_26") (pintype "passive"))
    )
    (net (code "33") (name "/PB14") (class "Default")
      (node (ref "R20") (pin "2") (pinfunction "2_2") (pintype "passive"))
      (node (ref "R22") (pin "1") (pinfunction "1_1") (pintype "passive"))
      (node (ref "STM32") (pin "27") (pinfunction "27_27") (pintype "passive"))
    )
    (net (code "34") (name "/PB15") (class "Default")
      (node (ref "R11") (pin "2") (pinfunction "2_2") (pintype "passive"))
      (node (ref "R13") (pin "1") (pinfunction "1_1") (pintype "passive"))
      (node (ref "STM32") (pin "28") (pinfunction "28_28") (pintype "passive"))
    )
    (net (code "35") (name "/PC13") (class "Default")
      (node (ref "STM32") (pin "2") (pinfunction "2_2") (pintype "passive"))
    )
    (net (code "36") (name "/PC14") (class "Default")
      (node (ref "C6") (pin "1") (pinfunction "1_1") (pintype "passive"))
      (node (ref "STM32") (pin "3") (pinfunction "3_3") (pintype "passive"))
      (node (ref "XTAL_32") (pin "2") (pinfunction "2_2") (pintype "passive"))
    )
    (net (code "37") (name "/PC15") (class "Default")
      (node (ref "C7") (pin "1") (pinfunction "1_1") (pintype "passive"))
      (node (ref "STM32") (pin "4") (pinfunction "4_4") (pintype "passive"))
      (node (ref "XTAL_32") (pin "1") (pinfunction "1_1") (pintype "passive"))
    )
    (net (code "38") (name "/PD0") (class "Default")
      (node (ref "C4") (pin "1") (pinfunction "1_1") (pintype "passive"))
      (node (ref "STM32") (pin "5") (pinfunction "5_5") (pintype "passive"))
      (node (ref "XTAL") (pin "2") (pinfunction "2_2") (pintype "passive"))
    )
    (net (code "39") (name "/PD1") (class "Default")
      (node (ref "C5") (pin "1") (pinfunction "1_1") (pintype "passive"))
      (node (ref "STM32") (pin "6") (pinfunction "6_6") (pintype "passive"))
      (node (ref "XTAL") (pin "1") (pinfunction "1_1") (pintype "passive"))
    )
    (net (code "40") (name "/U") (class "Default")
      (node (ref "INA_U") (pin "3") (pinfunction "V_IN+_3") (pintype "passive"))
      (node (ref "OUT") (pin "3") (pinfunction "3_3") (pintype "passive"))
      (node (ref "R_S_U") (pin "2") (pinfunction "2_2") (pintype "passive"))
      (node (ref "R_U1") (pin "1") (pinfunction "1_1") (pintype "passive"))
    )
    (net (code "41") (name "/U_PHASE") (class "Default")
      (node (ref "C8") (pin "2") (pinfunction "2_2") (pintype "passive"))
      (node (ref "CP1") (pin "2") (pinfunction "2_2") (pintype "passive"))
      (node (ref "FET1") (pin "3") (pinfunction "S_3") (pintype "passive"))
      (node (ref "FET2") (pin "2") (pinfunction "D_2") (pintype "passive"))
      (node (ref "INA_U") (pin "4") (pinfunction "V_IN-_4") (pintype "passive"))
      (node (ref "Q3") (pin "2") (pinfunction "C_2") (pintype "passive"))
      (node (ref "R8") (pin "2") (pinfunction "2_2") (pintype "passive"))
      (node (ref "R_S_U") (pin "1") (pinfunction "1_1") (pintype "passive"))
    )
    (net (code "42") (name "/V") (class "Default")
      (node (ref "INA_V") (pin "3") (pinfunction "V_IN+_3") (pintype "passive"))
      (node (ref "OUT") (pin "2") (pinfunction "2_2") (pintype "passive"))
      (node (ref "R_S_V") (pin "2") (pinfunction "2_2") (pintype "passive"))
      (node (ref "R_V1") (pin "1") (pinfunction "1_1") (pintype "passive"))
    )
    (net (code "43") (name "/V_PHASE") (class "Default")
      (node (ref "C10") (pin "2") (pinfunction "2_2") (pintype "passive"))
      (node (ref "CP2") (pin "2") (pinfunction "2_2") (pintype "passive"))
      (node (ref "FET3") (pin "3") (pinfunction "S_3") (pintype "passive"))
      (node (ref "FET4") (pin "2") (pinfunction "D_2") (pintype "passive"))
      (node (ref "INA_V") (pin "4") (pinfunction "V_IN-_4") (pintype "passive"))
      (node (ref "Q9") (pin "2") (pinfunction "C_2") (pintype "passive"))
      (node (ref "R17") (pin "2") (pinfunction "2_2") (pintype "passive"))
      (node (ref "R_S_V") (pin "1") (pinfunction "1_1") (pintype "passive"))
    )
    (net (code "44") (name "/W") (class "Default")
      (node (ref "INA_W") (pin "3") (pinfunction "V_IN+_3") (pintype "passive"))
      (node (ref "OUT") (pin "1") (pinfunction "1_1") (pintype "passive"))
      (node (ref "R_S_W") (pin "2") (pinfunction "2_2") (pintype "passive"))
      (node (ref "R_W1") (pin "1") (pinfunction "1_1") (pintype "passive"))
    )
    (net (code "45") (name "/W_PHASE") (class "Default")
      (node (ref "C12") (pin "2") (pinfunction "2_2") (pintype "passive"))
      (node (ref "CP3") (pin "2") (pinfunction "2_2") (pintype "passive"))
      (node (ref "FET5") (pin "3") (pinfunction "S_3") (pintype "passive"))
      (node (ref "FET6") (pin "2") (pinfunction "D_2") (pintype "passive"))
      (node (ref "INA_W") (pin "4") (pinfunction "V_IN-_4") (pintype "passive"))
      (node (ref "Q15") (pin "2") (pinfunction "C_2") (pintype "passive"))
      (node (ref "R26") (pin "2") (pinfunction "2_2") (pintype "passive"))
      (node (ref "R_S_W") (pin "1") (pinfunction "1_1") (pintype "passive"))
    )
    (net (code "46") (name "5V") (class "Default")
      (node (ref "Buck 3.3V") (pin "1") (pinfunction "In_1") (pintype "passive"))
      (node (ref "Buck5V") (pin "4") (pinfunction "FB_4") (pintype "input"))
      (node (ref "C_out_2") (pin "1") (pinfunction "1_1") (pintype "passive"))
      (node (ref "L2") (pin "2") (pinfunction "2_2") (pintype "passive"))
      (node (ref "LED_5V") (pin "1") (pinfunction "1_1") (pintype "passive"))
    )
    (net (code "47") (name "15V") (class "Default")
      (node (ref "Buck5V") (pin "1") (pinfunction "VIN_1") (pintype "power_in"))
      (node (ref "C_out_1") (pin "1") (pinfunction "1_1") (pintype "passive"))
      (node (ref "L1") (pin "2") (pinfunction "2_2") (pintype "passive"))
      (node (ref "LED15V") (pin "1") (pinfunction "1_1") (pintype "passive"))
      (node (ref "Q10") (pin "1") (pinfunction "E_1") (pintype "passive"))
      (node (ref "Q16") (pin "1") (pinfunction "E_1") (pintype "passive"))
      (node (ref "Q4") (pin "1") (pinfunction "E_1") (pintype "passive"))
      (node (ref "R10") (pin "1") (pinfunction "1_1") (pintype "passive"))
      (node (ref "R19") (pin "1") (pinfunction "1_1") (pintype "passive"))
      (node (ref "R28") (pin "1") (pinfunction "1_1") (pintype "passive"))
      (node (ref "R2_LM1") (pin "1") (pinfunction "1_1") (pintype "passive"))
    )
    (net (code "48") (name "24V") (class "Default")
      (node (ref "FET1") (pin "2") (pinfunction "D_2") (pintype "passive"))
      (node (ref "FET3") (pin "2") (pinfunction "D_2") (pintype "passive"))
      (node (ref "FET5") (pin "2") (pinfunction "D_2") (pintype "passive"))
    )
    (net (code "49") (name "GND") (class "Default")
      (node (ref "Buck15V") (pin "3") (pinfunction "GND_3") (pintype "power_in"))
      (node (ref "Buck15V") (pin "5") (pinfunction "~{ON}/OFF_5") (pintype "input"))
      (node (ref "Buck5V") (pin "3") (pinfunction "GND_3") (pintype "power_in"))
      (node (ref "Buck5V") (pin "5") (pinfunction "~{ON}/OFF_5") (pintype "input"))
      (node (ref "C_U") (pin "1") (pinfunction "1_1") (pintype "passive"))
      (node (ref "C_V") (pin "1") (pinfunction "1_1") (pintype "passive"))
      (node (ref "C_Vin") (pin "1") (pinfunction "1_1") (pintype "passive"))
      (node (ref "C_W") (pin "1") (pinfunction "1_1") (pintype "passive"))
      (node (ref "C_in_1") (pin "2") (pinfunction "2_2") (pintype "passive"))
      (node (ref "C_out_1") (pin "2") (pinfunction "2_2") (pintype "passive"))
      (node (ref "C_out_2") (pin "2") (pinfunction "2_2") (pintype "passive"))
      (node (ref "JP1") (pin "1") (pinfunction "1_1") (pintype "passive"))
      (node (ref "Q11") (pin "1") (pinfunction "E_1") (pintype "passive"))
      (node (ref "Q17") (pin "1") (pinfunction "E_1") (pintype "passive"))
      (node (ref "Q5") (pin "1") (pinfunction "E_1") (pintype "passive"))
      (node (ref "R0") (pin "1") (pinfunction "1_1") (pintype "passive"))
      (node (ref "R16") (pin "2") (pinfunction "2_2") (pintype "passive"))
      (node (ref "R1_LM1") (pin "2") (pinfunction "2_2") (pintype "passive"))
      (node (ref "R25") (pin "2") (pinfunction "2_2") (pintype "passive"))
      (node (ref "R7") (pin "2") (pinfunction "2_2") (pintype "passive"))
      (node (ref "R_S") (pin "2") (pinfunction "2_2") (pintype "passive"))
      (node (ref "R_U2") (pin "2") (pinfunction "2_2") (pintype "passive"))
      (node (ref "R_V2") (pin "2") (pinfunction "2_2") (pintype "passive"))
      (node (ref "R_Vin2") (pin "2") (pinfunction "2_2") (pintype "passive"))
      (node (ref "R_W2") (pin "2") (pinfunction "2_2") (pintype "passive"))
      (node (ref "diot") (pin "1") (pinfunction "A_1") (pintype "passive"))
      (node (ref "diot_1") (pin "1") (pinfunction "A_1") (pintype "passive"))
    )
    (net (code "50") (name "GND_1") (class "Default")
      (node (ref "BOOT") (pin "3") (pinfunction "3_3") (pintype "passive"))
      (node (ref "BOOT") (pin "4") (pinfunction "4_4") (pintype "passive"))
      (node (ref "Buck 3.3V") (pin "2") (pinfunction "Gnd_2") (pintype "passive"))
      (node (ref "C1") (pin "1") (pinfunction "1_1") (pintype "passive"))
      (node (ref "C2") (pin "1") (pinfunction "1_1") (pintype "passive"))
      (node (ref "C3") (pin "1") (pinfunction "1_1") (pintype "passive"))
      (node (ref "C4") (pin "2") (pinfunction "2_2") (pintype "passive"))
      (node (ref "C5") (pin "2") (pinfunction "2_2") (pintype "passive"))
      (node (ref "C6") (pin "2") (pinfunction "2_2") (pintype "passive"))
      (node (ref "C7") (pin "2") (pinfunction "2_2") (pintype "passive"))
      (node (ref "C_SW2") (pin "1") (pinfunction "1_1") (pintype "passive"))
      (node (ref "C_SW3") (pin "1") (pinfunction "1_1") (pintype "passive"))
      (node (ref "INA_U") (pin "2") (pinfunction "GND_2") (pintype "passive"))
      (node (ref "INA_V") (pin "2") (pinfunction "GND_2") (pintype "passive"))
      (node (ref "INA_W") (pin "2") (pinfunction "GND_2") (pintype "passive"))
      (node (ref "R0") (pin "2") (pinfunction "2_2") (pintype "passive"))
      (node (ref "R_LED15V") (pin "2") (pinfunction "2_2") (pintype "passive"))
      (node (ref "R_LED2") (pin "2") (pinfunction "2_2") (pintype "passive"))
      (node (ref "R_LED3") (pin "2") (pinfunction "2_2") (pintype "passive"))
      (node (ref "R_LED3.3V") (pin "2") (pinfunction "2_2") (pintype "passive"))
      (node (ref "R_LED5V") (pin "2") (pinfunction "2_2") (pintype "passive"))
      (node (ref "R_LED_Vin") (pin "2") (pinfunction "2_2") (pintype "passive"))
      (node (ref "STM32") (pin "23") (pinfunction "23_23") (pintype "passive"))
      (node (ref "STM32") (pin "35") (pinfunction "35_35") (pintype "passive"))
      (node (ref "STM32") (pin "47") (pinfunction "47_47") (pintype "passive"))
      (node (ref "STM32") (pin "8") (pinfunction "8_8") (pintype "passive"))
      (node (ref "SW1") (pin "1") (pinfunction "1_1") (pintype "passive"))
      (node (ref "SW2") (pin "1") (pinfunction "1_1") (pintype "passive"))
      (node (ref "SW3") (pin "1") (pinfunction "1_1") (pintype "passive"))
      (node (ref "SWD") (pin "1") (pinfunction "1_1") (pintype "passive"))
    )
    (net (code "51") (name "Net-(BOOT-Pad2)") (class "Default")
      (node (ref "BOOT") (pin "2") (pinfunction "2_2") (pintype "passive"))
      (node (ref "R2") (pin "2") (pinfunction "2_2") (pintype "passive"))
    )
    (net (code "52") (name "Net-(BOOT-Pad5)") (class "Default")
      (node (ref "BOOT") (pin "5") (pinfunction "5_5") (pintype "passive"))
      (node (ref "R3") (pin "2") (pinfunction "2_2") (pintype "passive"))
    )
    (net (code "53") (name "Net-(Buck5V-OUT)") (class "Default")
      (node (ref "Buck5V") (pin "2") (pinfunction "OUT_2") (pintype "power_in"))
      (node (ref "L2") (pin "1") (pinfunction "1_1") (pintype "passive"))
      (node (ref "diot") (pin "2") (pinfunction "K_2") (pintype "passive"))
    )
    (net (code "54") (name "Net-(Buck15V-FB)") (class "Default")
      (node (ref "Buck15V") (pin "4") (pinfunction "FB_4") (pintype "input"))
      (node (ref "R1_LM1") (pin "1") (pinfunction "1_1") (pintype "passive"))
      (node (ref "R2_LM1") (pin "2") (pinfunction "2_2") (pintype "passive"))
    )
    (net (code "55") (name "Net-(Buck15V-OUT)") (class "Default")
      (node (ref "Buck15V") (pin "2") (pinfunction "OUT_2") (pintype "power_in"))
      (node (ref "L1") (pin "1") (pinfunction "1_1") (pintype "passive"))
      (node (ref "diot_1") (pin "2") (pinfunction "K_2") (pintype "passive"))
    )
    (net (code "56") (name "Net-(D1-A)") (class "Default")
      (node (ref "D1") (pin "1") (pinfunction "A_1") (pintype "passive"))
      (node (ref "Q2") (pin "2") (pinfunction "C_2") (pintype "passive"))
      (node (ref "Q3") (pin "3") (pinfunction "B_3") (pintype "passive"))
      (node (ref "R8") (pin "1") (pinfunction "1_1") (pintype "passive"))
    )
    (net (code "57") (name "Net-(D1-K)") (class "Default")
      (node (ref "D1") (pin "2") (pinfunction "K_2") (pintype "passive"))
      (node (ref "R9") (pin "1") (pinfunction "1_1") (pintype "passive"))
    )
    (net (code "58") (name "Net-(D2-K)") (class "Default")
      (node (ref "CP1") (pin "1") (pinfunction "1_1") (pintype "passive"))
      (node (ref "D2") (pin "2") (pinfunction "K_2") (pintype "passive"))
      (node (ref "Q2") (pin "1") (pinfunction "E_1") (pintype "passive"))
      (node (ref "R6") (pin "1") (pinfunction "1_1") (pintype "passive"))
    )
    (net (code "59") (name "Net-(D3-A)") (class "Default")
      (node (ref "D3") (pin "1") (pinfunction "A_1") (pintype "passive"))
      (node (ref "Q8") (pin "2") (pinfunction "C_2") (pintype "passive"))
      (node (ref "Q9") (pin "3") (pinfunction "B_3") (pintype "passive"))
      (node (ref "R17") (pin "1") (pinfunction "1_1") (pintype "passive"))
    )
    (net (code "60") (name "Net-(D3-K)") (class "Default")
      (node (ref "D3") (pin "2") (pinfunction "K_2") (pintype "passive"))
      (node (ref "R18") (pin "1") (pinfunction "1_1") (pintype "passive"))
    )
    (net (code "61") (name "Net-(D4-K)") (class "Default")
      (node (ref "CP2") (pin "1") (pinfunction "1_1") (pintype "passive"))
      (node (ref "D4") (pin "2") (pinfunction "K_2") (pintype "passive"))
      (node (ref "Q8") (pin "1") (pinfunction "E_1") (pintype "passive"))
      (node (ref "R15") (pin "1") (pinfunction "1_1") (pintype "passive"))
    )
    (net (code "62") (name "Net-(D5-A)") (class "Default")
      (node (ref "D5") (pin "1") (pinfunction "A_1") (pintype "passive"))
      (node (ref "Q14") (pin "2") (pinfunction "C_2") (pintype "passive"))
      (node (ref "Q15") (pin "3") (pinfunction "B_3") (pintype "passive"))
      (node (ref "R26") (pin "1") (pinfunction "1_1") (pintype "passive"))
    )
    (net (code "63") (name "Net-(D5-K)") (class "Default")
      (node (ref "D5") (pin "2") (pinfunction "K_2") (pintype "passive"))
      (node (ref "R27") (pin "1") (pinfunction "1_1") (pintype "passive"))
    )
    (net (code "64") (name "Net-(D6-K)") (class "Default")
      (node (ref "CP3") (pin "1") (pinfunction "1_1") (pintype "passive"))
      (node (ref "D6") (pin "2") (pinfunction "K_2") (pintype "passive"))
      (node (ref "Q14") (pin "1") (pinfunction "E_1") (pintype "passive"))
      (node (ref "R24") (pin "1") (pinfunction "1_1") (pintype "passive"))
    )
    (net (code "65") (name "Net-(FET1-G)") (class "Default")
      (node (ref "C8") (pin "1") (pinfunction "1_1") (pintype "passive"))
      (node (ref "FET1") (pin "1") (pinfunction "G_1") (pintype "passive"))
      (node (ref "Q3") (pin "1") (pinfunction "E_1") (pintype "passive"))
      (node (ref "R9") (pin "2") (pinfunction "2_2") (pintype "passive"))
    )
    (net (code "66") (name "Net-(FET2-G)") (class "Default")
      (node (ref "C9") (pin "1") (pinfunction "1_1") (pintype "passive"))
      (node (ref "FET2") (pin "1") (pinfunction "G_1") (pintype "passive"))
      (node (ref "Q5") (pin "2") (pinfunction "C_2") (pintype "passive"))
      (node (ref "R12") (pin "2") (pinfunction "2_2") (pintype "passive"))
    )
    (net (code "67") (name "Net-(FET2-S)") (class "Default")
      (node (ref "C11") (pin "2") (pinfunction "2_2") (pintype "passive"))
      (node (ref "C13") (pin "2") (pinfunction "2_2") (pintype "passive"))
      (node (ref "C9") (pin "2") (pinfunction "2_2") (pintype "passive"))
      (node (ref "FET2") (pin "3") (pinfunction "S_3") (pintype "passive"))
      (node (ref "FET4") (pin "3") (pinfunction "S_3") (pintype "passive"))
      (node (ref "FET6") (pin "3") (pinfunction "S_3") (pintype "passive"))
      (node (ref "R_S") (pin "1") (pinfunction "1_1") (pintype "passive"))
    )
    (net (code "68") (name "Net-(FET3-G)") (class "Default")
      (node (ref "C10") (pin "1") (pinfunction "1_1") (pintype "passive"))
      (node (ref "FET3") (pin "1") (pinfunction "G_1") (pintype "passive"))
      (node (ref "Q9") (pin "1") (pinfunction "E_1") (pintype "passive"))
      (node (ref "R18") (pin "2") (pinfunction "2_2") (pintype "passive"))
    )
    (net (code "69") (name "Net-(FET4-G)") (class "Default")
      (node (ref "C11") (pin "1") (pinfunction "1_1") (pintype "passive"))
      (node (ref "FET4") (pin "1") (pinfunction "G_1") (pintype "passive"))
      (node (ref "Q11") (pin "2") (pinfunction "C_2") (pintype "passive"))
      (node (ref "R21") (pin "2") (pinfunction "2_2") (pintype "passive"))
    )
    (net (code "70") (name "Net-(FET5-G)") (class "Default")
      (node (ref "C12") (pin "1") (pinfunction "1_1") (pintype "passive"))
      (node (ref "FET5") (pin "1") (pinfunction "G_1") (pintype "passive"))
      (node (ref "Q15") (pin "1") (pinfunction "E_1") (pintype "passive"))
      (node (ref "R27") (pin "2") (pinfunction "2_2") (pintype "passive"))
    )
    (net (code "71") (name "Net-(FET6-G)") (class "Default")
      (node (ref "C13") (pin "1") (pinfunction "1_1") (pintype "passive"))
      (node (ref "FET6") (pin "1") (pinfunction "G_1") (pintype "passive"))
      (node (ref "Q17") (pin "2") (pinfunction "C_2") (pintype "passive"))
      (node (ref "R30") (pin "2") (pinfunction "2_2") (pintype "passive"))
    )
    (net (code "72") (name "Net-(FUSE-Pad1)") (class "Default")
      (node (ref "FUSE") (pin "1") (pinfunction "1_1") (pintype "passive"))
      (node (ref "JP1") (pin "2") (pinfunction "2_2") (pintype "passive"))
    )
    (net (code "73") (name "Net-(INA_U-OUT)") (class "Default")
      (node (ref "INA_U") (pin "1") (pinfunction "OUT_1") (pintype "passive"))
      (node (ref "R_ADCU") (pin "1") (pinfunction "1_1") (pintype "passive"))
    )
    (net (code "74") (name "Net-(INA_V-OUT)") (class "Default")
      (node (ref "INA_V") (pin "1") (pinfunction "OUT_1") (pintype "passive"))
      (node (ref "R_ADCV") (pin "1") (pinfunction "1_1") (pintype "passive"))
    )
    (net (code "75") (name "Net-(INA_W-OUT)") (class "Default")
      (node (ref "INA_W") (pin "1") (pinfunction "OUT_1") (pintype "passive"))
      (node (ref "R_ADCW") (pin "1") (pinfunction "1_1") (pintype "passive"))
    )
    (net (code "76") (name "Net-(LED2-Pad2)") (class "Default")
      (node (ref "LED2") (pin "2") (pinfunction "2_2") (pintype "passive"))
      (node (ref "R_LED2") (pin "1") (pinfunction "1_1") (pintype "passive"))
    )
    (net (code "77") (name "Net-(LED3-Pad2)") (class "Default")
      (node (ref "LED3") (pin "2") (pinfunction "2_2") (pintype "passive"))
      (node (ref "R_LED3") (pin "1") (pinfunction "1_1") (pintype "passive"))
    )
    (net (code "78") (name "Net-(LED3.3V-Pad2)") (class "Default")
      (node (ref "LED3.3V") (pin "2") (pinfunction "2_2") (pintype "passive"))
      (node (ref "R_LED3.3V") (pin "1") (pinfunction "1_1") (pintype "passive"))
    )
    (net (code "79") (name "Net-(LED15V-Pad2)") (class "Default")
      (node (ref "LED15V") (pin "2") (pinfunction "2_2") (pintype "passive"))
      (node (ref "R_LED15V") (pin "1") (pinfunction "1_1") (pintype "passive"))
    )
    (net (code "80") (name "Net-(LED_5V-Pad2)") (class "Default")
      (node (ref "LED_5V") (pin "2") (pinfunction "2_2") (pintype "passive"))
      (node (ref "R_LED5V") (pin "1") (pinfunction "1_1") (pintype "passive"))
    )
    (net (code "81") (name "Net-(LED_Vin-Pad2)") (class "Default")
      (node (ref "LED_Vin") (pin "2") (pinfunction "2_2") (pintype "passive"))
      (node (ref "R_LED_Vin") (pin "1") (pinfunction "1_1") (pintype "passive"))
    )
    (net (code "82") (name "Net-(Q1-B)") (class "Default")
      (node (ref "Q1") (pin "3") (pinfunction "B_3") (pintype "passive"))
      (node (ref "R5") (pin "1") (pinfunction "1_1") (pintype "passive"))
    )
    (net (code "83") (name "Net-(Q1-C)") (class "Default")
      (node (ref "Q1") (pin "2") (pinfunction "C_2") (pintype "passive"))
      (node (ref "Q2") (pin "3") (pinfunction "B_3") (pintype "passive"))
      (node (ref "R6") (pin "2") (pinfunction "2_2") (pintype "passive"))
    )
    (net (code "84") (name "Net-(Q1-E)") (class "Default")
      (node (ref "Q1") (pin "1") (pinfunction "E_1") (pintype "passive"))
      (node (ref "R7") (pin "1") (pinfunction "1_1") (pintype "passive"))
    )
    (net (code "85") (name "Net-(Q4-B)") (class "Default")
      (node (ref "Q4") (pin "3") (pinfunction "B_3") (pintype "passive"))
      (node (ref "Q6") (pin "2") (pinfunction "C_2") (pintype "passive"))
      (node (ref "R10") (pin "2") (pinfunction "2_2") (pintype "passive"))
    )
    (net (code "86") (name "Net-(Q4-C)") (class "Default")
      (node (ref "Q4") (pin "2") (pinfunction "C_2") (pintype "passive"))
      (node (ref "R12") (pin "1") (pinfunction "1_1") (pintype "passive"))
    )
    (net (code "87") (name "Net-(Q5-B)") (class "Default")
      (node (ref "Q5") (pin "3") (pinfunction "B_3") (pintype "passive"))
      (node (ref "R13") (pin "2") (pinfunction "2_2") (pintype "passive"))
    )
    (net (code "88") (name "Net-(Q6-E)") (class "Default")
      (node (ref "Q6") (pin "1") (pinfunction "E_1") (pintype "passive"))
      (node (ref "R11") (pin "1") (pinfunction "1_1") (pintype "passive"))
    )
    (net (code "89") (name "Net-(Q7-B)") (class "Default")
      (node (ref "Q7") (pin "3") (pinfunction "B_3") (pintype "passive"))
      (node (ref "R14") (pin "1") (pinfunction "1_1") (pintype "passive"))
    )
    (net (code "90") (name "Net-(Q7-C)") (class "Default")
      (node (ref "Q7") (pin "2") (pinfunction "C_2") (pintype "passive"))
      (node (ref "Q8") (pin "3") (pinfunction "B_3") (pintype "passive"))
      (node (ref "R15") (pin "2") (pinfunction "2_2") (pintype "passive"))
    )
    (net (code "91") (name "Net-(Q7-E)") (class "Default")
      (node (ref "Q7") (pin "1") (pinfunction "E_1") (pintype "passive"))
      (node (ref "R16") (pin "1") (pinfunction "1_1") (pintype "passive"))
    )
    (net (code "92") (name "Net-(Q10-B)") (class "Default")
      (node (ref "Q10") (pin "3") (pinfunction "B_3") (pintype "passive"))
      (node (ref "Q12") (pin "2") (pinfunction "C_2") (pintype "passive"))
      (node (ref "R19") (pin "2") (pinfunction "2_2") (pintype "passive"))
    )
    (net (code "93") (name "Net-(Q10-C)") (class "Default")
      (node (ref "Q10") (pin "2") (pinfunction "C_2") (pintype "passive"))
      (node (ref "R21") (pin "1") (pinfunction "1_1") (pintype "passive"))
    )
    (net (code "94") (name "Net-(Q11-B)") (class "Default")
      (node (ref "Q11") (pin "3") (pinfunction "B_3") (pintype "passive"))
      (node (ref "R22") (pin "2") (pinfunction "2_2") (pintype "passive"))
    )
    (net (code "95") (name "Net-(Q12-E)") (class "Default")
      (node (ref "Q12") (pin "1") (pinfunction "E_1") (pintype "passive"))
      (node (ref "R20") (pin "1") (pinfunction "1_1") (pintype "passive"))
    )
    (net (code "96") (name "Net-(Q13-B)") (class "Default")
      (node (ref "Q13") (pin "3") (pinfunction "B_3") (pintype "passive"))
      (node (ref "R23") (pin "1") (pinfunction "1_1") (pintype "passive"))
    )
    (net (code "97") (name "Net-(Q13-C)") (class "Default")
      (node (ref "Q13") (pin "2") (pinfunction "C_2") (pintype "passive"))
      (node (ref "Q14") (pin "3") (pinfunction "B_3") (pintype "passive"))
      (node (ref "R24") (pin "2") (pinfunction "2_2") (pintype "passive"))
    )
    (net (code "98") (name "Net-(Q13-E)") (class "Default")
      (node (ref "Q13") (pin "1") (pinfunction "E_1") (pintype "passive"))
      (node (ref "R25") (pin "1") (pinfunction "1_1") (pintype "passive"))
    )
    (net (code "99") (name "Net-(Q16-B)") (class "Default")
      (node (ref "Q16") (pin "3") (pinfunction "B_3") (pintype "passive"))
      (node (ref "Q18") (pin "2") (pinfunction "C_2") (pintype "passive"))
      (node (ref "R28") (pin "2") (pinfunction "2_2") (pintype "passive"))
    )
    (net (code "100") (name "Net-(Q16-C)") (class "Default")
      (node (ref "Q16") (pin "2") (pinfunction "C_2") (pintype "passive"))
      (node (ref "R30") (pin "1") (pinfunction "1_1") (pintype "passive"))
    )
    (net (code "101") (name "Net-(Q17-B)") (class "Default")
      (node (ref "Q17") (pin "3") (pinfunction "B_3") (pintype "passive"))
      (node (ref "R31") (pin "2") (pinfunction "2_2") (pintype "passive"))
    )
    (net (code "102") (name "Net-(Q18-E)") (class "Default")
      (node (ref "Q18") (pin "1") (pinfunction "E_1") (pintype "passive"))
      (node (ref "R29") (pin "1") (pinfunction "1_1") (pintype "passive"))
    )
    (net (code "103") (name "Net-(R_RS_2-Pad2)") (class "Default")
      (node (ref "R_RS_2") (pin "2") (pinfunction "2_2") (pintype "passive"))
      (node (ref "SW1") (pin "2") (pinfunction "2_2") (pintype "passive"))
    )
    (net (code "104") (name "Net-(R_SW2_2-Pad1)") (class "Default")
      (node (ref "R_SW2_2") (pin "1") (pinfunction "1_1") (pintype "passive"))
      (node (ref "SW2") (pin "2") (pinfunction "2_2") (pintype "passive"))
    )
    (net (code "105") (name "Net-(R_SW3_2-Pad1)") (class "Default")
      (node (ref "R_SW3_2") (pin "1") (pinfunction "1_1") (pintype "passive"))
      (node (ref "SW3") (pin "2") (pinfunction "2_2") (pintype "passive"))
    )
    (net (code "106") (name "VCC3V3") (class "Default")
      (node (ref "BOOT") (pin "1") (pinfunction "1_1") (pintype "passive"))
      (node (ref "BOOT") (pin "6") (pinfunction "6_6") (pintype "passive"))
      (node (ref "Buck 3.3V") (pin "3") (pinfunction "Out_3") (pintype "passive"))
      (node (ref "C2") (pin "2") (pinfunction "2_2") (pintype "passive"))
      (node (ref "C3") (pin "2") (pinfunction "2_2") (pintype "passive"))
      (node (ref "INA_U") (pin "5") (pinfunction "VCC_5") (pintype "passive"))
      (node (ref "INA_V") (pin "5") (pinfunction "VCC_5") (pintype "passive"))
      (node (ref "INA_W") (pin "5") (pinfunction "VCC_5") (pintype "passive"))
      (node (ref "LED3.3V") (pin "1") (pinfunction "1_1") (pintype "passive"))
      (node (ref "Q12") (pin "3") (pinfunction "B_3") (pintype "passive"))
      (node (ref "Q18") (pin "3") (pinfunction "B_3") (pintype "passive"))
      (node (ref "Q6") (pin "3") (pinfunction "B_3") (pintype "passive"))
      (node (ref "R_RS_1") (pin "1") (pinfunction "1_1") (pintype "passive"))
      (node (ref "R_SW2_1") (pin "1") (pinfunction "1_1") (pintype "passive"))
      (node (ref "R_SW3_1") (pin "1") (pinfunction "1_1") (pintype "passive"))
      (node (ref "STM32") (pin "1") (pinfunction "1_1") (pintype "passive"))
      (node (ref "STM32") (pin "24") (pinfunction "24_24") (pintype "passive"))
      (node (ref "STM32") (pin "36") (pinfunction "36_36") (pintype "passive"))
      (node (ref "STM32") (pin "48") (pinfunction "48_48") (pintype "passive"))
      (node (ref "STM32") (pin "9") (pinfunction "9_9") (pintype "passive"))
      (node (ref "SWD") (pin "4") (pinfunction "4_4") (pintype "passive"))
    )
    (net (code "107") (name "V_IN") (class "Default")
      (node (ref "Buck15V") (pin "1") (pinfunction "VIN_1") (pintype "power_in"))
      (node (ref "C_in_1") (pin "1") (pinfunction "1_1") (pintype "passive"))
      (node (ref "D2") (pin "1") (pinfunction "A_1") (pintype "passive"))
      (node (ref "D4") (pin "1") (pinfunction "A_1") (pintype "passive"))
      (node (ref "D6") (pin "1") (pinfunction "A_1") (pintype "passive"))
      (node (ref "FUSE") (pin "2") (pinfunction "2_2") (pintype "passive"))
      (node (ref "LED_Vin") (pin "1") (pinfunction "1_1") (pintype "passive"))
      (node (ref "R_Vin1") (pin "1") (pinfunction "1_1") (pintype "passive"))
    )
  )
)
